# ZYNQ_PL_Bank_33.net
KiCad netlist of a schematic drawn in Altium Designer
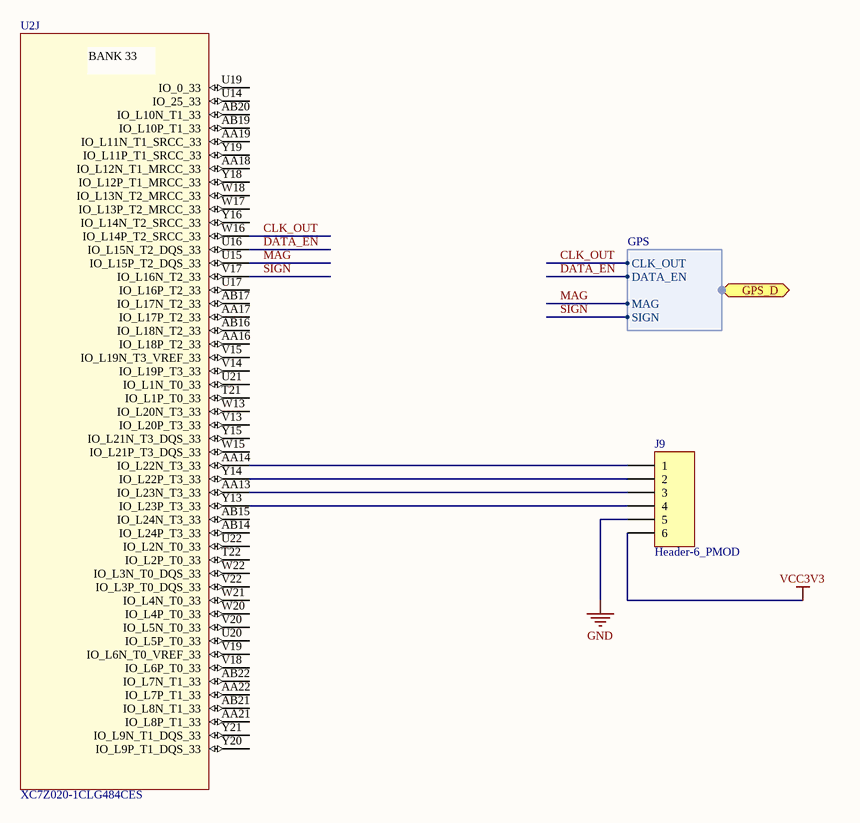
[diagram p0: ZYNQ_PL_Bank_33.SchDoc]

(export (version "E")
  (design (tool "Eeschema 10.0.6"))
  (components
    (comp (ref "J9")
      (value "Header-6_PMOD")
      (footprint "ConnectorGPIO_Sullins_PPTC061LGBN-RC_6-pos")
      (description "CONN FEMALE 6POS .100\" R/A TIN")
      (fields
        (field (name "PART NUMBER") "PPTC061LGBN-RC")
        (field (name "MANUFACTURER") "Sullins Connector Solutions")
      )
      (libsource (lib "COMRAD_Database") (part "Header-6_PMOD"))
    )
    (comp (ref "U2")
      (value "XC7Z020-1CLG484CES")
      (footprint "ZYNQ_xc7z020clg484pkg_BGA-484")
      (description "XC7Z020-1CLG484CES, Zynq-7000 All Programmable SoC")
      (fields (field (name "MANUFACTURER") "Xilinx"))
      (libsource (lib "COMRAD_Database") (part "ZYNQ_XC7Z020CLG484PKG"))
    )
  )
  (nets
    (net (code "2") (name "/CLK_OUT") (class "Default")
      (node (ref "U2") (pin "W16") (pinfunction "IO_L14P_T2_SRCC_33_W16") (pintype "bidirectional"))
    )
    (net (code "3") (name "/DATA_EN") (class "Default")
      (node (ref "U2") (pin "U16") (pinfunction "IO_L15N_T2_DQS_33_U16") (pintype "bidirectional"))
    )
    (net (code "4") (name "/MAG") (class "Default")
      (node (ref "U2") (pin "U15") (pinfunction "IO_L15P_T2_DQS_33_U15") (pintype "bidirectional"))
    )
    (net (code "5") (name "/SIGN") (class "Default")
      (node (ref "U2") (pin "V17") (pinfunction "IO_L16N_T2_33_V17") (pintype "bidirectional"))
    )
    (net (code "7") (name "GND") (class "Default")
      (node (ref "J9") (pin "5") (pinfunction "5_5") (pintype "passive"))
    )
    (net (code "8") (name "Net-(U2J-IO_L22N_T3_33)") (class "Default")
      (node (ref "J9") (pin "1") (pinfunction "1_1") (pintype "passive"))
      (node (ref "U2") (pin "AA14") (pinfunction "IO_L22N_T3_33_AA14") (pintype "bidirectional"))
    )
    (net (code "9") (name "Net-(U2J-IO_L22P_T3_33)") (class "Default")
      (node (ref "J9") (pin "2") (pinfunction "2_2") (pintype "passive"))
      (node (ref "U2") (pin "Y14") (pinfunction "IO_L22P_T3_33_Y14") (pintype "bidirectional"))
    )
    (net (code "10") (name "Net-(U2J-IO_L23N_T3_33)") (class "Default")
      (node (ref "J9") (pin "3") (pinfunction "3_3") (pintype "passive"))
      (node (ref "U2") (pin "AA13") (pinfunction "IO_L23N_T3_33_AA13") (pintype "bidirectional"))
    )
    (net (code "11") (name "Net-(U2J-IO_L23P_T3_33)") (class "Default")
      (node (ref "J9") (pin "4") (pinfunction "4_4") (pintype "passive"))
      (node (ref "U2") (pin "Y13") (pinfunction "IO_L23P_T3_33_Y13") (pintype "bidirectional"))
    )
    (net (code "12") (name "VCC3V3") (class "Default")
      (node (ref "J9") (pin "6") (pinfunction "6_6") (pintype "passive"))
    )
    (net (code "13") (name "unconnected-(U2J-IO_0_33-PadU19)") (class "Default")
      (node (ref "U2") (pin "U19") (pinfunction "IO_0_33_U19") (pintype "bidirectional"))
    )
    (net (code "14") (name "unconnected-(U2J-IO_25_33-PadU14)") (class "Default")
      (node (ref "U2") (pin "U14") (pinfunction "IO_25_33_U14") (pintype "bidirectional"))
    )
    (net (code "15") (name "unconnected-(U2J-IO_L1N_T0_33-PadU21)") (class "Default")
      (node (ref "U2") (pin "U21") (pinfunction "IO_L1N_T0_33_U21") (pintype "bidirectional"))
    )
    (net (code "16") (name "unconnected-(U2J-IO_L1P_T0_33-PadT21)") (class "Default")
      (node (ref "U2") (pin "T21") (pinfunction "IO_L1P_T0_33_T21") (pintype "bidirectional"))
    )
    (net (code "17") (name "unconnected-(U2J-IO_L2N_T0_33-PadU22)") (class "Default")
      (node (ref "U2") (pin "U22") (pinfunction "IO_L2N_T0_33_U22") (pintype "bidirectional"))
    )
    (net (code "18") (name "unconnected-(U2J-IO_L2P_T0_33-PadT22)") (class "Default")
      (node (ref "U2") (pin "T22") (pinfunction "IO_L2P_T0_33_T22") (pintype "bidirectional"))
    )
    (net (code "19") (name "unconnected-(U2J-IO_L3N_T0_DQS_33-PadW22)") (class "Default")
      (node (ref "U2") (pin "W22") (pinfunction "IO_L3N_T0_DQS_33_W22") (pintype "bidirectional"))
    )
    (net (code "20") (name "unconnected-(U2J-IO_L3P_T0_DQS_33-PadV22)") (class "Default")
      (node (ref "U2") (pin "V22") (pinfunction "IO_L3P_T0_DQS_33_V22") (pintype "bidirectional"))
    )
    (net (code "21") (name "unconnected-(U2J-IO_L4N_T0_33-PadW21)") (class "Default")
      (node (ref "U2") (pin "W21") (pinfunction "IO_L4N_T0_33_W21") (pintype "bidirectional"))
    )
    (net (code "22") (name "unconnected-(U2J-IO_L4P_T0_33-PadW20)") (class "Default")
      (node (ref "U2") (pin "W20") (pinfunction "IO_L4P_T0_33_W20") (pintype "bidirectional"))
    )
    (net (code "23") (name "unconnected-(U2J-IO_L5N_T0_33-PadV20)") (class "Default")
      (node (ref "U2") (pin "V20") (pinfunction "IO_L5N_T0_33_V20") (pintype "bidirectional"))
    )
    (net (code "24") (name "unconnected-(U2J-IO_L5P_T0_33-PadU20)") (class "Default")
      (node (ref "U2") (pin "U20") (pinfunction "IO_L5P_T0_33_U20") (pintype "bidirectional"))
    )
    (net (code "25") (name "unconnected-(U2J-IO_L6N_T0_VREF_33-PadV19)") (class "Default")
      (node (ref "U2") (pin "V19") (pinfunction "IO_L6N_T0_VREF_33_V19") (pintype "bidirectional"))
    )
    (net (code "26") (name "unconnected-(U2J-IO_L6P_T0_33-PadV18)") (class "Default")
      (node (ref "U2") (pin "V18") (pinfunction "IO_L6P_T0_33_V18") (pintype "bidirectional"))
    )
    (net (code "27") (name "unconnected-(U2J-IO_L7N_T1_33-PadAB22)") (class "Default")
      (node (ref "U2") (pin "AB22") (pinfunction "IO_L7N_T1_33_AB22") (pintype "bidirectional"))
    )
    (net (code "28") (name "unconnected-(U2J-IO_L7P_T1_33-PadAA22)") (class "Default")
      (node (ref "U2") (pin "AA22") (pinfunction "IO_L7P_T1_33_AA22") (pintype "bidirectional"))
    )
    (net (code "29") (name "unconnected-(U2J-IO_L8N_T1_33-PadAB21)") (class "Default")
      (node (ref "U2") (pin "AB21") (pinfunction "IO_L8N_T1_33_AB21") (pintype "bidirectional"))
    )
    (net (code "30") (name "unconnected-(U2J-IO_L8P_T1_33-PadAA21)") (class "Default")
      (node (ref "U2") (pin "AA21") (pinfunction "IO_L8P_T1_33_AA21") (pintype "bidirectional"))
    )
    (net (code "31") (name "unconnected-(U2J-IO_L9N_T1_DQS_33-PadY21)") (class "Default")
      (node (ref "U2") (pin "Y21") (pinfunction "IO_L9N_T1_DQS_33_Y21") (pintype "bidirectional"))
    )
    (net (code "32") (name "unconnected-(U2J-IO_L9P_T1_DQS_33-PadY20)") (class "Default")
      (node (ref "U2") (pin "Y20") (pinfunction "IO_L9P_T1_DQS_33_Y20") (pintype "bidirectional"))
    )
    (net (code "33") (name "unconnected-(U2J-IO_L10N_T1_33-PadAB20)") (class "Default")
      (node (ref "U2") (pin "AB20") (pinfunction "IO_L10N_T1_33_AB20") (pintype "bidirectional"))
    )
    (net (code "34") (name "unconnected-(U2J-IO_L10P_T1_33-PadAB19)") (class "Default")
      (node (ref "U2") (pin "AB19") (pinfunction "IO_L10P_T1_33_AB19") (pintype "bidirectional"))
    )
    (net (code "35") (name "unconnected-(U2J-IO_L11N_T1_SRCC_33-PadAA19)") (class "Default")
      (node (ref "U2") (pin "AA19") (pinfunction "IO_L11N_T1_SRCC_33_AA19") (pintype "bidirectional"))
    )
    (net (code "36") (name "unconnected-(U2J-IO_L11P_T1_SRCC_33-PadY19)") (class "Default")
      (node (ref "U2") (pin "Y19") (pinfunction "IO_L11P_T1_SRCC_33_Y19") (pintype "bidirectional"))
    )
    (net (code "37") (name "unconnected-(U2J-IO_L12N_T1_MRCC_33-PadAA18)") (class "Default")
      (node (ref "U2") (pin "AA18") (pinfunction "IO_L12N_T1_MRCC_33_AA18") (pintype "bidirectional"))
    )
    (net (code "38") (name "unconnected-(U2J-IO_L12P_T1_MRCC_33-PadY18)") (class "Default")
      (node (ref "U2") (pin "Y18") (pinfunction "IO_L12P_T1_MRCC_33_Y18") (pintype "bidirectional"))
    )
    (net (code "39") (name "unconnected-(U2J-IO_L13N_T2_MRCC_33-PadW18)") (class "Default")
      (node (ref "U2") (pin "W18") (pinfunction "IO_L13N_T2_MRCC_33_W18") (pintype "bidirectional"))
    )
    (net (code "40") (name "unconnected-(U2J-IO_L13P_T2_MRCC_33-PadW17)") (class "Default")
      (node (ref "U2") (pin "W17") (pinfunction "IO_L13P_T2_MRCC_33_W17") (pintype "bidirectional"))
    )
    (net (code "41") (name "unconnected-(U2J-IO_L14N_T2_SRCC_33-PadY16)") (class "Default")
      (node (ref "U2") (pin "Y16") (pinfunction "IO_L14N_T2_SRCC_33_Y16") (pintype "bidirectional"))
    )
    (net (code "42") (name "unconnected-(U2J-IO_L16P_T2_33-PadU17)") (class "Default")
      (node (ref "U2") (pin "U17") (pinfunction "IO_L16P_T2_33_U17") (pintype "bidirectional"))
    )
    (net (code "43") (name "unconnected-(U2J-IO_L17N_T2_33-PadAB17)") (class "Default")
      (node (ref "U2") (pin "AB17") (pinfunction "IO_L17N_T2_33_AB17") (pintype "bidirectional"))
    )
    (net (code "44") (name "unconnected-(U2J-IO_L17P_T2_33-PadAA17)") (class "Default")
      (node (ref "U2") (pin "AA17") (pinfunction "IO_L17P_T2_33_AA17") (pintype "bidirectional"))
    )
    (net (code "45") (name "unconnected-(U2J-IO_L18N_T2_33-PadAB16)") (class "Default")
      (node (ref "U2") (pin "AB16") (pinfunction "IO_L18N_T2_33_AB16") (pintype "bidirectional"))
    )
    (net (code "46") (name "unconnected-(U2J-IO_L18P_T2_33-PadAA16)") (class "Default")
      (node (ref "U2") (pin "AA16") (pinfunction "IO_L18P_T2_33_AA16") (pintype "bidirectional"))
    )
    (net (code "47") (name "unconnected-(U2J-IO_L19N_T3_VREF_33-PadV15)") (class "Default")
      (node (ref "U2") (pin "V15") (pinfunction "IO_L19N_T3_VREF_33_V15") (pintype "bidirectional"))
    )
    (net (code "48") (name "unconnected-(U2J-IO_L19P_T3_33-PadV14)") (class "Default")
      (node (ref "U2") (pin "V14") (pinfunction "IO_L19P_T3_33_V14") (pintype "bidirectional"))
    )
    (net (code "49") (name "unconnected-(U2J-IO_L20N_T3_33-PadW13)") (class "Default")
      (node (ref "U2") (pin "W13") (pinfunction "IO_L20N_T3_33_W13") (pintype "bidirectional"))
    )
    (net (code "50") (name "unconnected-(U2J-IO_L20P_T3_33-PadV13)") (class "Default")
      (node (ref "U2") (pin "V13") (pinfunction "IO_L20P_T3_33_V13") (pintype "bidirectional"))
    )
    (net (code "51") (name "unconnected-(U2J-IO_L21N_T3_DQS_33-PadY15)") (class "Default")
      (node (ref "U2") (pin "Y15") (pinfunction "IO_L21N_T3_DQS_33_Y15") (pintype "bidirectional"))
    )
    (net (code "52") (name "unconnected-(U2J-IO_L21P_T3_DQS_33-PadW15)") (class "Default")
      (node (ref "U2") (pin "W15") (pinfunction "IO_L21P_T3_DQS_33_W15") (pintype "bidirectional"))
    )
    (net (code "53") (name "unconnected-(U2J-IO_L24N_T3_33-PadAB15)") (class "Default")
      (node (ref "U2") (pin "AB15") (pinfunction "IO_L24N_T3_33_AB15") (pintype "bidirectional"))
    )
    (net (code "54") (name "unconnected-(U2J-IO_L24P_T3_33-PadAB14)") (class "Default")
      (node (ref "U2") (pin "AB14") (pinfunction "IO_L24P_T3_33_AB14") (pintype "bidirectional"))
    )
  )
)
